# C-Core.net
KiCad netlist of a schematic drawn in Altium Designer
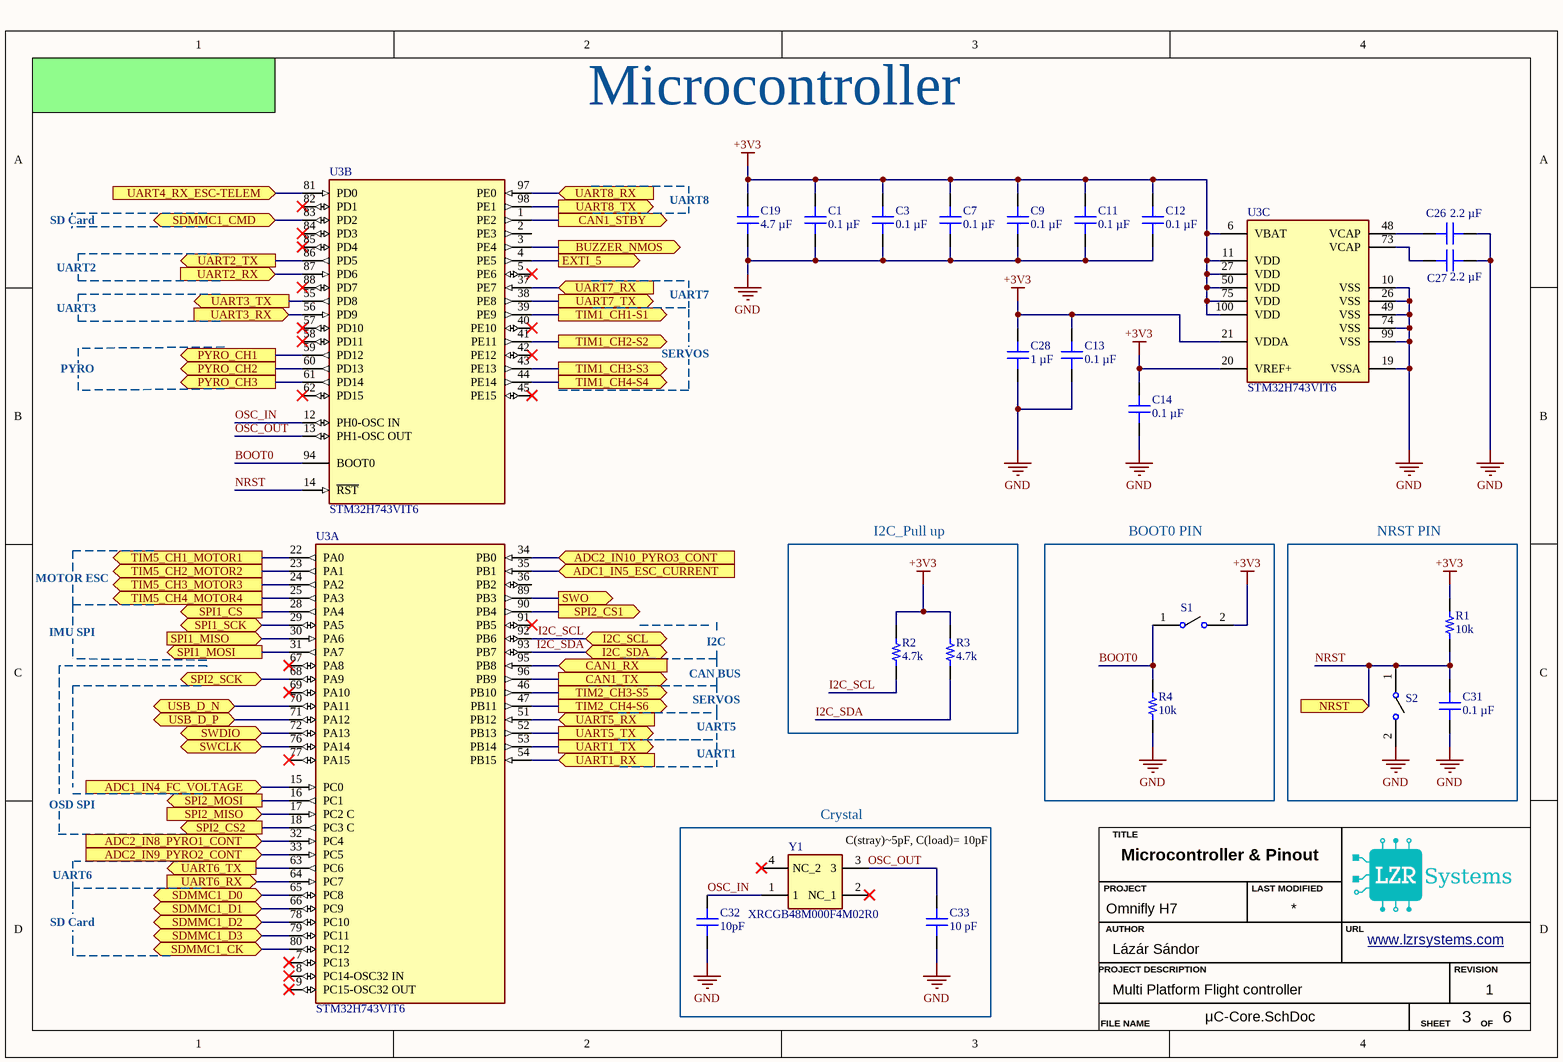
[diagram p0: μC-Core.SchDoc]

(export (version "E")
  (design (tool "Eeschema 10.0.6"))
  (components
    (comp (ref "C1")
      (value "0.1 µF")
      (footprint "MURATA GCM155 0402_1005")
      (description "CAP CER 0.1UF 50V X7R 0402")
      (fields
        (field (name "PART NUMBER") "GCM155R71H104ME02D")
        (field (name "CAPACITANCE") "0.1 µF")
        (field (name "MANUFACTURER") "Murata Electronics")
      )
      (libsource (lib "Celestial Altium Library - altium_library") (part "Capacitor"))
    )
    (comp (ref "C3")
      (value "0.1 µF")
      (footprint "MURATA GCM155 0402_1005")
      (description "CAP CER 0.1UF 50V X7R 0402")
      (fields
        (field (name "PART NUMBER") "GCM155R71H104ME02D")
        (field (name "CAPACITANCE") "0.1 µF")
        (field (name "MANUFACTURER") "Murata Electronics")
      )
      (libsource (lib "Celestial Altium Library - altium_library") (part "Capacitor"))
    )
    (comp (ref "C7")
      (value "0.1 µF")
      (footprint "MURATA GCM155 0402_1005")
      (description "CAP CER 0.1UF 50V X7R 0402")
      (fields
        (field (name "PART NUMBER") "GCM155R71H104ME02D")
        (field (name "CAPACITANCE") "0.1 µF")
        (field (name "MANUFACTURER") "Murata Electronics")
      )
      (libsource (lib "Celestial Altium Library - altium_library") (part "Capacitor"))
    )
    (comp (ref "C9")
      (value "0.1 µF")
      (footprint "MURATA GCM155 0402_1005")
      (description "CAP CER 0.1UF 50V X7R 0402")
      (fields
        (field (name "PART NUMBER") "GCM155R71H104ME02D")
        (field (name "CAPACITANCE") "0.1 µF")
        (field (name "MANUFACTURER") "Murata Electronics")
      )
      (libsource (lib "Celestial Altium Library - altium_library") (part "Capacitor"))
    )
    (comp (ref "C11")
      (value "0.1 µF")
      (footprint "MURATA GCM155 0402_1005")
      (description "CAP CER 0.1UF 50V X7R 0402")
      (fields
        (field (name "PART NUMBER") "GCM155R71H104ME02D")
        (field (name "CAPACITANCE") "0.1 µF")
        (field (name "MANUFACTURER") "Murata Electronics")
      )
      (libsource (lib "Celestial Altium Library - altium_library") (part "Capacitor"))
    )
    (comp (ref "C12")
      (value "0.1 µF")
      (footprint "MURATA GCM155 0402_1005")
      (description "CAP CER 0.1UF 50V X7R 0402")
      (fields
        (field (name "PART NUMBER") "GCM155R71H104ME02D")
        (field (name "CAPACITANCE") "0.1 µF")
        (field (name "MANUFACTURER") "Murata Electronics")
      )
      (libsource (lib "Celestial Altium Library - altium_library") (part "Capacitor"))
    )
    (comp (ref "C13")
      (value "0.1 µF")
      (footprint "MURATA GCM155 0402_1005")
      (description "CAP CER 0.1UF 50V X7R 0402")
      (fields
        (field (name "PART NUMBER") "GCM155R71H104ME02D")
        (field (name "CAPACITANCE") "0.1 µF")
        (field (name "MANUFACTURER") "Murata Electronics")
      )
      (libsource (lib "Celestial Altium Library - altium_library") (part "Capacitor"))
    )
    (comp (ref "C14")
      (value "0.1 µF")
      (footprint "MURATA GCM155 0402_1005")
      (description "CAP CER 0.1UF 50V X7R 0402")
      (fields
        (field (name "PART NUMBER") "GCM155R71H104ME02D")
        (field (name "CAPACITANCE") "0.1 µF")
        (field (name "MANUFACTURER") "Murata Electronics")
      )
      (libsource (lib "Celestial Altium Library - altium_library") (part "Capacitor"))
    )
    (comp (ref "C19")
      (value "4.7 µF")
      (footprint "MURATA GRM21B 0805_2012")
      (description "CAP CER 4.7UF 50V X5R 0805")
      (fields
        (field (name "PART NUMBER") "GRM21BR61H475KE51L")
        (field (name "CAPACITANCE") "4.7 µF")
        (field (name "MANUFACTURER") "Murata Electronics")
      )
      (libsource (lib "Celestial Altium Library - altium_library") (part "Capacitor"))
    )
    (comp (ref "C26")
      (value "2.2 µF")
      (footprint "CAP 0805_2012")
      (description "CAP CER 2.2UF 35V X8L 0805")
      (fields
        (field (name "PART NUMBER") "GCM21BL8EG225KE07L")
        (field (name "CAPACITANCE") "2.2 µF")
        (field (name "MANUFACTURER") "Murata Electronics")
      )
      (libsource (lib "Celestial Altium Library - altium_library") (part "Capacitor"))
    )
    (comp (ref "C27")
      (value "2.2 µF")
      (footprint "CAP 0805_2012")
      (description "CAP CER 2.2UF 35V X8L 0805")
      (fields
        (field (name "PART NUMBER") "GCM21BL8EG225KE07L")
        (field (name "CAPACITANCE") "2.2 µF")
        (field (name "MANUFACTURER") "Murata Electronics")
      )
      (libsource (lib "Celestial Altium Library - altium_library") (part "Capacitor"))
    )
    (comp (ref "C28")
      (value "1 µF")
      (footprint "CAP 0805_2012")
      (description "CAP CER 1UF 35V X7R 0805")
      (fields
        (field (name "PART NUMBER") "GRM219R7YA105MA12D")
        (field (name "CAPACITANCE") "1 µF")
        (field (name "MANUFACTURER") "Murata Electronics")
      )
      (libsource (lib "Celestial Altium Library - altium_library") (part "Capacitor"))
    )
    (comp (ref "C31")
      (value "0.1 µF")
      (footprint "MURATA GCM155 0402_1005")
      (description "CAP CER 0.1UF 50V X7R 0402")
      (fields
        (field (name "PART NUMBER") "GCM155R71H104ME02D")
        (field (name "CAPACITANCE") "0.1 µF")
        (field (name "MANUFACTURER") "Murata Electronics")
      )
      (libsource (lib "Celestial Altium Library - altium_library") (part "Capacitor"))
    )
    (comp (ref "C32")
      (value "10 pF")
      (footprint "CAP 0402_1005")
      (description "CAP CER 10PF 16V C0G/NP0 0402")
      (fields
        (field (name "PART NUMBER") "C0402C100K4GAC7867")
        (field (name "CAPACITANCE") "10pF")
        (field (name "MANUFACTURER") "KEMET")
      )
      (libsource (lib "Celestial Altium Library - altium_library") (part "Capacitor"))
    )
    (comp (ref "C33")
      (value "10 pF")
      (footprint "CAP 0402_1005")
      (description "CAP CER 10PF 16V C0G/NP0 0402")
      (fields
        (field (name "PART NUMBER") "C0402C100K4GAC7867")
        (field (name "CAPACITANCE") "10 pF")
        (field (name "MANUFACTURER") "KEMET")
      )
      (libsource (lib "Celestial Altium Library - altium_library") (part "Capacitor"))
    )
    (comp (ref "R1")
      (value "10k")
      (footprint "YAGEO RES 0402_1005")
      (description "RES 10K OHM 0.5% 1/16W 0402")
      (fields (field (name "PART NUMBER") "AC0402DR-0710KL") (field (name "MANUFACTURER") "Yageo"))
      (libsource (lib "Celestial Altium Library - altium_library") (part "Resistor"))
    )
    (comp (ref "R2")
      (value "4.7k")
      (footprint "YAGEO RES 0402_1005")
      (description "RES 4.7K OHM 1% 1/16W 0402")
      (fields (field (name "PART NUMBER") "AC0402FR-134K7L") (field (name "MANUFACTURER") "Yageo"))
      (libsource (lib "Celestial Altium Library - altium_library") (part "Resistor"))
    )
    (comp (ref "R3")
      (value "4.7k")
      (footprint "YAGEO RES 0402_1005")
      (description "RES 4.7K OHM 1% 1/16W 0402")
      (fields (field (name "PART NUMBER") "AC0402FR-134K7L") (field (name "MANUFACTURER") "Yageo"))
      (libsource (lib "Celestial Altium Library - altium_library") (part "Resistor"))
    )
    (comp (ref "R4")
      (value "10k")
      (footprint "YAGEO RES 0402_1005")
      (description "RES 10K OHM 0.5% 1/16W 0402")
      (fields (field (name "PART NUMBER") "AC0402DR-0710KL") (field (name "MANUFACTURER") "Yageo"))
      (libsource (lib "Celestial Altium Library - altium_library") (part "Resistor"))
    )
    (comp (ref "S1")
      (value "TS09-63-25-WT-160-SMT-TR")
      (footprint "SamacSys:TS096325WT160SMTTR")
      (description "Switch")
      (fields (field (name "MOUSER PART NUMBER") "179-TS0925WT160SMTTR"))
      (libsource (lib "SamacSys") (part "TS09-63-25-WT-160-SMT-TR"))
    )
    (comp (ref "S2")
      (value "TS09-63-25-WT-160-SMT-TR")
      (footprint "SamacSys:TS096325WT160SMTTR")
      (description "Switch")
      (fields (field (name "MOUSER PART NUMBER") "179-TS0925WT160SMTTR"))
      (libsource (lib "SamacSys") (part "TS09-63-25-WT-160-SMT-TR"))
    )
    (comp (ref "U3")
      (value "STM32H743VIT6")
      (footprint "FP-LQFP100-1L-IPC_C")
      (description "RISC Microcontroller, 32-Bit, FLASH, CORTEX-M7 CPU, 480MHz, CMOS, PQFP100")
      (libsource (lib "Sandor Lazar") (part "01082ce2885d1d16a22823c45526fe6"))
    )
    (comp (ref "Y1")
      (value "XRCGB48M000F4M02R0")
      (footprint "SamacSys:XRCGB")
      (description "Crystal or Oscillator")
      (fields
        (field (name "MANUFACTURER_PART_NUMBER") "XRCGB48M000F4M00R0")
        (field (name "MOUSER PART NUMBER") "81-XRCGB48M000F4M0R0")
      )
      (libsource (lib "SamacSys") (part "XRCGB48M000F4M00R0"))
    )
  )
  (nets
    (net (code "1") (name "+3V3") (class "Default")
      (node (ref "C1") (pin "2") (pinfunction "2_2") (pintype "passive"))
      (node (ref "C11") (pin "2") (pinfunction "2_2") (pintype "passive"))
      (node (ref "C12") (pin "2") (pinfunction "2_2") (pintype "passive"))
      (node (ref "C13") (pin "2") (pinfunction "2_2") (pintype "passive"))
      (node (ref "C14") (pin "2") (pinfunction "2_2") (pintype "passive"))
      (node (ref "C19") (pin "2") (pinfunction "2_2") (pintype "passive"))
      (node (ref "C28") (pin "2") (pinfunction "2_2") (pintype "passive"))
      (node (ref "C3") (pin "2") (pinfunction "2_2") (pintype "passive"))
      (node (ref "C7") (pin "2") (pinfunction "2_2") (pintype "passive"))
      (node (ref "C9") (pin "2") (pinfunction "2_2") (pintype "passive"))
      (node (ref "R1") (pin "1") (pinfunction "1_1") (pintype "passive"))
      (node (ref "R2") (pin "2") (pinfunction "2_2") (pintype "passive"))
      (node (ref "R3") (pin "2") (pinfunction "2_2") (pintype "passive"))
      (node (ref "S1") (pin "2") (pinfunction "NO_2") (pintype "passive"))
      (node (ref "U3") (pin "100") (pinfunction "VDD_100") (pintype "power_in"))
      (node (ref "U3") (pin "11") (pinfunction "VDD_11") (pintype "power_in"))
      (node (ref "U3") (pin "20") (pinfunction "VREF+_20") (pintype "power_in"))
      (node (ref "U3") (pin "21") (pinfunction "VDDA_21") (pintype "power_in"))
      (node (ref "U3") (pin "27") (pinfunction "VDD_27") (pintype "power_in"))
      (node (ref "U3") (pin "50") (pinfunction "VDD_50") (pintype "power_in"))
      (node (ref "U3") (pin "6") (pinfunction "VBAT_6") (pintype "power_in"))
      (node (ref "U3") (pin "75") (pinfunction "VDD_75") (pintype "power_in"))
    )
    (net (code "2") (name "/ADC1_IN4_FC_VOLTAGE") (class "Default")
      (node (ref "U3") (pin "15") (pinfunction "PC0_15") (pintype "input"))
    )
    (net (code "3") (name "/ADC1_IN5_ESC_CURRENT") (class "Default")
      (node (ref "U3") (pin "35") (pinfunction "PB1_35") (pintype "input"))
    )
    (net (code "4") (name "/ADC2_IN8_PYRO1_CONT") (class "Default")
      (node (ref "U3") (pin "32") (pinfunction "PC4_32") (pintype "input"))
    )
    (net (code "5") (name "/ADC2_IN9_PYRO2_CONT") (class "Default")
      (node (ref "U3") (pin "33") (pinfunction "PC5_33") (pintype "input"))
    )
    (net (code "6") (name "/ADC2_IN10_PYRO3_CONT") (class "Default")
      (node (ref "U3") (pin "34") (pinfunction "PB0_34") (pintype "input"))
    )
    (net (code "7") (name "/BOOT0") (class "Default")
      (node (ref "R4") (pin "1") (pinfunction "1_1") (pintype "passive"))
      (node (ref "S1") (pin "1") (pinfunction "COM_1") (pintype "passive"))
      (node (ref "U3") (pin "94") (pinfunction "BOOT0_94") (pintype "input"))
    )
    (net (code "8") (name "/BUZZER_NMOS") (class "Default")
      (node (ref "U3") (pin "3") (pinfunction "PE4_3") (pintype "bidirectional"))
    )
    (net (code "9") (name "/CAN1_RX") (class "Default")
      (node (ref "U3") (pin "95") (pinfunction "PB8_95") (pintype "input"))
    )
    (net (code "10") (name "/CAN1_STBY") (class "Default")
      (node (ref "U3") (pin "1") (pinfunction "PE2_1") (pintype "bidirectional"))
    )
    (net (code "11") (name "/CAN1_TX") (class "Default")
      (node (ref "U3") (pin "96") (pinfunction "PB9_96") (pintype "output"))
    )
    (net (code "12") (name "/EXTI_5") (class "Default")
      (node (ref "U3") (pin "4") (pinfunction "PE5_4") (pintype "bidirectional"))
    )
    (net (code "13") (name "/I2C_SCL") (class "Default")
      (node (ref "R2") (pin "1") (pinfunction "1_1") (pintype "passive"))
      (node (ref "U3") (pin "92") (pinfunction "PB6_92") (pintype "bidirectional"))
    )
    (net (code "14") (name "/I2C_SDA") (class "Default")
      (node (ref "R3") (pin "1") (pinfunction "1_1") (pintype "passive"))
      (node (ref "U3") (pin "93") (pinfunction "PB7_93") (pintype "bidirectional"))
    )
    (net (code "15") (name "/NRST") (class "Default")
      (node (ref "C31") (pin "2") (pinfunction "2_2") (pintype "passive"))
      (node (ref "R1") (pin "2") (pinfunction "2_2") (pintype "passive"))
      (node (ref "S2") (pin "1") (pinfunction "COM_1") (pintype "passive"))
      (node (ref "U3") (pin "14") (pinfunction "~{RST}_14") (pintype "input"))
    )
    (net (code "16") (name "/OSC_IN") (class "Default")
      (node (ref "C32") (pin "2") (pinfunction "2_2") (pintype "passive"))
      (node (ref "U3") (pin "12") (pinfunction "PH0-OSC_IN_12") (pintype "bidirectional"))
      (node (ref "Y1") (pin "1") (pinfunction "1_1") (pintype "passive"))
    )
    (net (code "17") (name "/OSC_OUT") (class "Default")
      (node (ref "C33") (pin "2") (pinfunction "2_2") (pintype "passive"))
      (node (ref "U3") (pin "13") (pinfunction "PH1-OSC_OUT_13") (pintype "bidirectional"))
      (node (ref "Y1") (pin "3") (pinfunction "3_3") (pintype "passive"))
    )
    (net (code "18") (name "/PYRO_CH1") (class "Default")
      (node (ref "U3") (pin "59") (pinfunction "PD12_59") (pintype "bidirectional"))
    )
    (net (code "19") (name "/PYRO_CH2") (class "Default")
      (node (ref "U3") (pin "60") (pinfunction "PD13_60") (pintype "bidirectional"))
    )
    (net (code "20") (name "/PYRO_CH3") (class "Default")
      (node (ref "U3") (pin "61") (pinfunction "PD14_61") (pintype "bidirectional"))
    )
    (net (code "21") (name "/SDMMC1_CK") (class "Default")
      (node (ref "U3") (pin "80") (pinfunction "PC12_80") (pintype "bidirectional"))
    )
    (net (code "22") (name "/SDMMC1_CMD") (class "Default")
      (node (ref "U3") (pin "83") (pinfunction "PD2_83") (pintype "bidirectional"))
    )
    (net (code "23") (name "/SDMMC1_D0") (class "Default")
      (node (ref "U3") (pin "65") (pinfunction "PC8_65") (pintype "bidirectional"))
    )
    (net (code "24") (name "/SDMMC1_D1") (class "Default")
      (node (ref "U3") (pin "66") (pinfunction "PC9_66") (pintype "bidirectional"))
    )
    (net (code "25") (name "/SDMMC1_D2") (class "Default")
      (node (ref "U3") (pin "78") (pinfunction "PC10_78") (pintype "bidirectional"))
    )
    (net (code "26") (name "/SDMMC1_D3") (class "Default")
      (node (ref "U3") (pin "79") (pinfunction "PC11_79") (pintype "bidirectional"))
    )
    (net (code "27") (name "/SPI1_CS") (class "Default")
      (node (ref "U3") (pin "28") (pinfunction "PA4_28") (pintype "output"))
    )
    (net (code "28") (name "/SPI1_MISO") (class "Default")
      (node (ref "U3") (pin "30") (pinfunction "PA6_30") (pintype "input"))
    )
    (net (code "29") (name "/SPI1_MOSI") (class "Default")
      (node (ref "U3") (pin "31") (pinfunction "PA7_31") (pintype "output"))
    )
    (net (code "30") (name "/SPI1_SCK") (class "Default")
      (node (ref "U3") (pin "29") (pinfunction "PA5_29") (pintype "bidirectional"))
    )
    (net (code "31") (name "/SPI2_CS1") (class "Default")
      (node (ref "U3") (pin "90") (pinfunction "PB4_90") (pintype "output"))
    )
    (net (code "32") (name "/SPI2_CS2") (class "Default")
      (node (ref "U3") (pin "18") (pinfunction "PC3_C_18") (pintype "output"))
    )
    (net (code "33") (name "/SPI2_MISO") (class "Default")
      (node (ref "U3") (pin "17") (pinfunction "PC2_C_17") (pintype "input"))
    )
    (net (code "34") (name "/SPI2_MOSI") (class "Default")
      (node (ref "U3") (pin "16") (pinfunction "PC1_16") (pintype "output"))
    )
    (net (code "35") (name "/SPI2_SCK") (class "Default")
      (node (ref "U3") (pin "68") (pinfunction "PA9_68") (pintype "bidirectional"))
    )
    (net (code "36") (name "/SWCLK") (class "Default")
      (node (ref "U3") (pin "76") (pinfunction "PA14_76") (pintype "bidirectional"))
    )
    (net (code "37") (name "/SWDIO") (class "Default")
      (node (ref "U3") (pin "72") (pinfunction "PA13_72") (pintype "bidirectional"))
    )
    (net (code "38") (name "/SWO") (class "Default")
      (node (ref "U3") (pin "89") (pinfunction "PB3_89") (pintype "output"))
    )
    (net (code "39") (name "/TIM1_CH1-S1") (class "Default")
      (node (ref "U3") (pin "39") (pinfunction "PE9_39") (pintype "bidirectional"))
    )
    (net (code "40") (name "/TIM1_CH2-S2") (class "Default")
      (node (ref "U3") (pin "41") (pinfunction "PE11_41") (pintype "bidirectional"))
    )
    (net (code "41") (name "/TIM1_CH3-S3") (class "Default")
      (node (ref "U3") (pin "43") (pinfunction "PE13_43") (pintype "bidirectional"))
    )
    (net (code "42") (name "/TIM1_CH4-S4") (class "Default")
      (node (ref "U3") (pin "44") (pinfunction "PE14_44") (pintype "bidirectional"))
    )
    (net (code "43") (name "/TIM2_CH3-S5") (class "Default")
      (node (ref "U3") (pin "46") (pinfunction "PB10_46") (pintype "output"))
    )
    (net (code "44") (name "/TIM2_CH4-S6") (class "Default")
      (node (ref "U3") (pin "47") (pinfunction "PB11_47") (pintype "output"))
    )
    (net (code "45") (name "/TIM5_CH1_MOTOR1") (class "Default")
      (node (ref "U3") (pin "22") (pinfunction "PA0_22") (pintype "output"))
    )
    (net (code "46") (name "/TIM5_CH2_MOTOR2") (class "Default")
      (node (ref "U3") (pin "23") (pinfunction "PA1_23") (pintype "output"))
    )
    (net (code "47") (name "/TIM5_CH3_MOTOR3") (class "Default")
      (node (ref "U3") (pin "24") (pinfunction "PA2_24") (pintype "output"))
    )
    (net (code "48") (name "/TIM5_CH4_MOTOR4") (class "Default")
      (node (ref "U3") (pin "25") (pinfunction "PA3_25") (pintype "output"))
    )
    (net (code "49") (name "/UART1_RX") (class "Default")
      (node (ref "U3") (pin "54") (pinfunction "PB15_54") (pintype "input"))
    )
    (net (code "50") (name "/UART1_TX") (class "Default")
      (node (ref "U3") (pin "53") (pinfunction "PB14_53") (pintype "output"))
    )
    (net (code "51") (name "/UART2_RX") (class "Default")
      (node (ref "U3") (pin "87") (pinfunction "PD6_87") (pintype "bidirectional"))
    )
    (net (code "52") (name "/UART2_TX") (class "Default")
      (node (ref "U3") (pin "86") (pinfunction "PD5_86") (pintype "bidirectional"))
    )
    (net (code "53") (name "/UART3_RX") (class "Default")
      (node (ref "U3") (pin "56") (pinfunction "PD9_56") (pintype "bidirectional"))
    )
    (net (code "54") (name "/UART3_TX") (class "Default")
      (node (ref "U3") (pin "55") (pinfunction "PD8_55") (pintype "bidirectional"))
    )
    (net (code "55") (name "/UART4_RX_ESC-TELEM") (class "Default")
      (node (ref "U3") (pin "81") (pinfunction "PD0_81") (pintype "bidirectional"))
    )
    (net (code "56") (name "/UART5_RX") (class "Default")
      (node (ref "U3") (pin "51") (pinfunction "PB12_51") (pintype "input"))
    )
    (net (code "57") (name "/UART5_TX") (class "Default")
      (node (ref "U3") (pin "52") (pinfunction "PB13_52") (pintype "output"))
    )
    (net (code "58") (name "/UART6_RX") (class "Default")
      (node (ref "U3") (pin "64") (pinfunction "PC7_64") (pintype "input"))
    )
    (net (code "59") (name "/UART6_TX") (class "Default")
      (node (ref "U3") (pin "63") (pinfunction "PC6_63") (pintype "output"))
    )
    (net (code "60") (name "/UART7_RX") (class "Default")
      (node (ref "U3") (pin "37") (pinfunction "PE7_37") (pintype "bidirectional"))
    )
    (net (code "61") (name "/UART7_TX") (class "Default")
      (node (ref "U3") (pin "38") (pinfunction "PE8_38") (pintype "bidirectional"))
    )
    (net (code "62") (name "/UART8_RX") (class "Default")
      (node (ref "U3") (pin "97") (pinfunction "PE0_97") (pintype "bidirectional"))
    )
    (net (code "63") (name "/UART8_TX") (class "Default")
      (node (ref "U3") (pin "98") (pinfunction "PE1_98") (pintype "bidirectional"))
    )
    (net (code "64") (name "/USB_D_N") (class "Default")
      (node (ref "U3") (pin "70") (pinfunction "PA11_70") (pintype "bidirectional"))
    )
    (net (code "65") (name "/USB_D_P") (class "Default")
      (node (ref "U3") (pin "71") (pinfunction "PA12_71") (pintype "bidirectional"))
    )
    (net (code "66") (name "GND") (class "Default")
      (node (ref "C1") (pin "1") (pinfunction "1_1") (pintype "passive"))
      (node (ref "C11") (pin "1") (pinfunction "1_1") (pintype "passive"))
      (node (ref "C12") (pin "1") (pinfunction "1_1") (pintype "passive"))
      (node (ref "C13") (pin "1") (pinfunction "1_1") (pintype "passive"))
      (node (ref "C14") (pin "1") (pinfunction "1_1") (pintype "passive"))
      (node (ref "C19") (pin "1") (pinfunction "1_1") (pintype "passive"))
      (node (ref "C26") (pin "2") (pinfunction "2_2") (pintype "passive"))
      (node (ref "C27") (pin "1") (pinfunction "1_1") (pintype "passive"))
      (node (ref "C28") (pin "1") (pinfunction "1_1") (pintype "passive"))
      (node (ref "C3") (pin "1") (pinfunction "1_1") (pintype "passive"))
      (node (ref "C31") (pin "1") (pinfunction "1_1") (pintype "passive"))
      (node (ref "C32") (pin "1") (pinfunction "1_1") (pintype "passive"))
      (node (ref "C33") (pin "1") (pinfunction "1_1") (pintype "passive"))
      (node (ref "C7") (pin "1") (pinfunction "1_1") (pintype "passive"))
      (node (ref "C9") (pin "1") (pinfunction "1_1") (pintype "passive"))
      (node (ref "R4") (pin "2") (pinfunction "2_2") (pintype "passive"))
      (node (ref "S2") (pin "2") (pinfunction "NO_2") (pintype "passive"))
      (node (ref "U3") (pin "10") (pinfunction "VSS_10") (pintype "power_in"))
      (node (ref "U3") (pin "19") (pinfunction "VSSA_19") (pintype "power_in"))
      (node (ref "U3") (pin "26") (pinfunction "VSS_26") (pintype "power_in"))
      (node (ref "U3") (pin "49") (pinfunction "VSS_49") (pintype "power_in"))
      (node (ref "U3") (pin "74") (pinfunction "VSS_74") (pintype "power_in"))
      (node (ref "U3") (pin "99") (pinfunction "VSS_99") (pintype "power_in"))
    )
    (net (code "67") (name "Net-(C26-Pad1)") (class "Default")
      (node (ref "C26") (pin "1") (pinfunction "1_1") (pintype "passive"))
      (node (ref "U3") (pin "48") (pinfunction "VCAP_48") (pintype "passive"))
    )
    (net (code "68") (name "Net-(C27-Pad2)") (class "Default")
      (node (ref "C27") (pin "2") (pinfunction "2_2") (pintype "passive"))
      (node (ref "U3") (pin "73") (pinfunction "VCAP_73") (pintype "passive"))
    )
    (net (code "69") (name "unconnected-(U3A-PA8-Pad67)") (class "Default")
      (node (ref "U3") (pin "67") (pinfunction "PA8_67") (pintype "bidirectional+no_connect"))
    )
    (net (code "70") (name "unconnected-(U3A-PA10-Pad69)") (class "Default")
      (node (ref "U3") (pin "69") (pinfunction "PA10_69") (pintype "bidirectional+no_connect"))
    )
    (net (code "71") (name "unconnected-(U3A-PA15-Pad77)") (class "Default")
      (node (ref "U3") (pin "77") (pinfunction "PA15_77") (pintype "bidirectional+no_connect"))
    )
    (net (code "72") (name "unconnected-(U3A-PB2-Pad36)") (class "Default")
      (node (ref "U3") (pin "36") (pinfunction "PB2_36") (pintype "bidirectional"))
    )
    (net (code "73") (name "unconnected-(U3A-PB5-Pad91)") (class "Default")
      (node (ref "U3") (pin "91") (pinfunction "PB5_91") (pintype "bidirectional+no_connect"))
    )
    (net (code "74") (name "unconnected-(U3A-PC13-Pad7)") (class "Default")
      (node (ref "U3") (pin "7") (pinfunction "PC13_7") (pintype "bidirectional+no_connect"))
    )
    (net (code "75") (name "unconnected-(U3A-PC14-OSC32_IN-Pad8)") (class "Default")
      (node (ref "U3") (pin "8") (pinfunction "PC14-OSC32_IN_8") (pintype "bidirectional+no_connect"))
    )
    (net (code "76") (name "unconnected-(U3A-PC15-OSC32_OUT-Pad9)") (class "Default")
      (node (ref "U3") (pin "9") (pinfunction "PC15-OSC32_OUT_9") (pintype "bidirectional+no_connect"))
    )
    (net (code "77") (name "unconnected-(U3B-PD1-Pad82)") (class "Default")
      (node (ref "U3") (pin "82") (pinfunction "PD1_82") (pintype "bidirectional+no_connect"))
    )
    (net (code "78") (name "unconnected-(U3B-PD3-Pad84)") (class "Default")
      (node (ref "U3") (pin "84") (pinfunction "PD3_84") (pintype "bidirectional+no_connect"))
    )
    (net (code "79") (name "unconnected-(U3B-PD4-Pad85)") (class "Default")
      (node (ref "U3") (pin "85") (pinfunction "PD4_85") (pintype "bidirectional+no_connect"))
    )
    (net (code "80") (name "unconnected-(U3B-PD7-Pad88)") (class "Default")
      (node (ref "U3") (pin "88") (pinfunction "PD7_88") (pintype "bidirectional+no_connect"))
    )
    (net (code "81") (name "unconnected-(U3B-PD10-Pad57)") (class "Default")
      (node (ref "U3") (pin "57") (pinfunction "PD10_57") (pintype "bidirectional+no_connect"))
    )
    (net (code "82") (name "unconnected-(U3B-PD11-Pad58)") (class "Default")
      (node (ref "U3") (pin "58") (pinfunction "PD11_58") (pintype "bidirectional+no_connect"))
    )
    (net (code "83") (name "unconnected-(U3B-PD15-Pad62)") (class "Default")
      (node (ref "U3") (pin "62") (pinfunction "PD15_62") (pintype "bidirectional+no_connect"))
    )
    (net (code "84") (name "unconnected-(U3B-PE3-Pad2)") (class "Default")
      (node (ref "U3") (pin "2") (pinfunction "PE3_2") (pintype "bidirectional"))
    )
    (net (code "85") (name "unconnected-(U3B-PE6-Pad5)") (class "Default")
      (node (ref "U3") (pin "5") (pinfunction "PE6_5") (pintype "bidirectional+no_connect"))
    )
    (net (code "86") (name "unconnected-(U3B-PE10-Pad40)") (class "Default")
      (node (ref "U3") (pin "40") (pinfunction "PE10_40") (pintype "bidirectional+no_connect"))
    )
    (net (code "87") (name "unconnected-(U3B-PE12-Pad42)") (class "Default")
      (node (ref "U3") (pin "42") (pinfunction "PE12_42") (pintype "bidirectional+no_connect"))
    )
    (net (code "88") (name "unconnected-(U3B-PE15-Pad45)") (class "Default")
      (node (ref "U3") (pin "45") (pinfunction "PE15_45") (pintype "bidirectional+no_connect"))
    )
    (net (code "89") (name "unconnected-(Y1-NC_1-Pad2)") (class "Default")
      (node (ref "Y1") (pin "2") (pinfunction "NC_1_2") (pintype "passive+no_connect"))
    )
    (net (code "90") (name "unconnected-(Y1-NC_2-Pad4)") (class "Default")
      (node (ref "Y1") (pin "4") (pinfunction "NC_2_4") (pintype "passive+no_connect"))
    )
  )
)
